# tdlf_01_04_2020_TOUCH.net
KiCad netlist of a schematic drawn in EAGLE
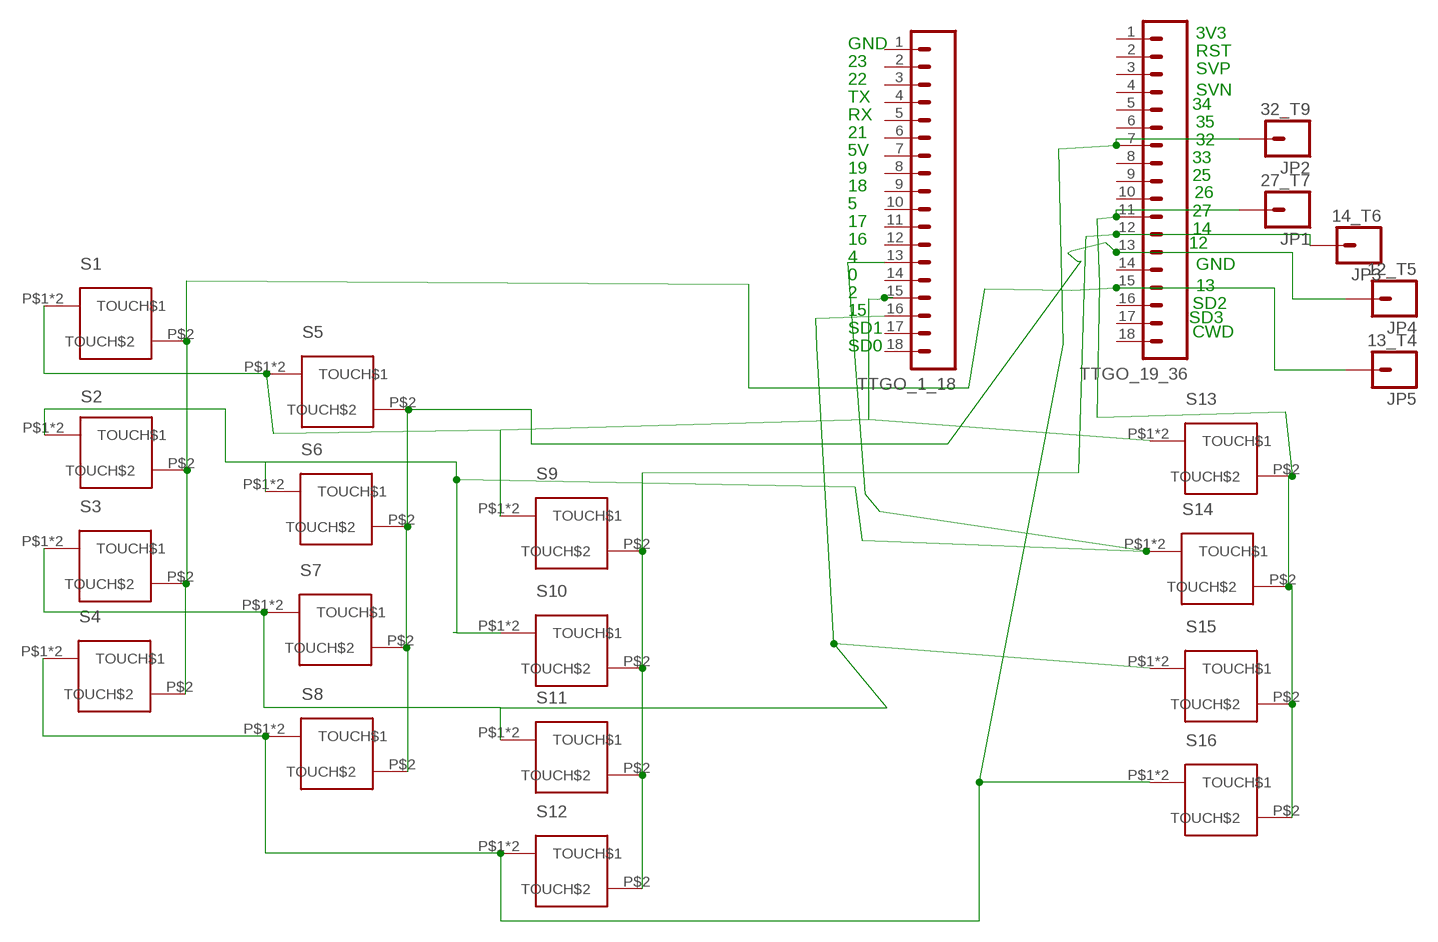
[diagram p0: schematic, sheet 1]

(export (version "E")
  (design (tool "Eeschema 10.0.6"))
  (components
    (comp (ref "JP1")
      (value "27_T7")
      (footprint "eagle-import:PAD-1.5X4.5")
      (libsource (lib "eagle-import") (part "M01SMD-4.5X1.5"))
    )
    (comp (ref "JP2")
      (value "32_T9")
      (footprint "eagle-import:PAD-1.5X4.5")
      (libsource (lib "eagle-import") (part "M01SMD-4.5X1.5"))
    )
    (comp (ref "JP3")
      (value "14_T6")
      (footprint "eagle-import:PAD-1.5X4.5")
      (libsource (lib "eagle-import") (part "M01SMD-4.5X1.5"))
    )
    (comp (ref "JP4")
      (value "12_T5")
      (footprint "eagle-import:PAD-1.5X4.5")
      (libsource (lib "eagle-import") (part "M01SMD-4.5X1.5"))
    )
    (comp (ref "JP5")
      (value "13_T4")
      (footprint "eagle-import:PAD-1.5X4.5")
      (libsource (lib "eagle-import") (part "M01SMD-4.5X1.5"))
    )
    (comp (ref "S1")
      (value "DUALCAPACITIVEBUTTON")
      (footprint "eagle-import:R1206")
      (libsource (lib "eagle-import") (part "DUALCAPACITIVEBUTTON"))
    )
    (comp (ref "S2")
      (value "DUALCAPACITIVEBUTTON")
      (footprint "eagle-import:R1206")
      (libsource (lib "eagle-import") (part "DUALCAPACITIVEBUTTON"))
    )
    (comp (ref "S3")
      (value "DUALCAPACITIVEBUTTON")
      (footprint "eagle-import:R1206")
      (libsource (lib "eagle-import") (part "DUALCAPACITIVEBUTTON"))
    )
    (comp (ref "S4")
      (value "DUALCAPACITIVEBUTTON")
      (footprint "eagle-import:R1206")
      (libsource (lib "eagle-import") (part "DUALCAPACITIVEBUTTON"))
    )
    (comp (ref "S5")
      (value "DUALCAPACITIVEBUTTON")
      (footprint "eagle-import:R1206")
      (libsource (lib "eagle-import") (part "DUALCAPACITIVEBUTTON"))
    )
    (comp (ref "S6")
      (value "DUALCAPACITIVEBUTTON")
      (footprint "eagle-import:R1206")
      (libsource (lib "eagle-import") (part "DUALCAPACITIVEBUTTON"))
    )
    (comp (ref "S7")
      (value "DUALCAPACITIVEBUTTON")
      (footprint "eagle-import:R1206")
      (libsource (lib "eagle-import") (part "DUALCAPACITIVEBUTTON"))
    )
    (comp (ref "S8")
      (value "DUALCAPACITIVEBUTTON")
      (footprint "eagle-import:R1206")
      (libsource (lib "eagle-import") (part "DUALCAPACITIVEBUTTON"))
    )
    (comp (ref "S9")
      (value "DUALCAPACITIVEBUTTON")
      (footprint "eagle-import:R1206")
      (libsource (lib "eagle-import") (part "DUALCAPACITIVEBUTTON"))
    )
    (comp (ref "S10")
      (value "DUALCAPACITIVEBUTTON")
      (footprint "eagle-import:R1206")
      (libsource (lib "eagle-import") (part "DUALCAPACITIVEBUTTON"))
    )
    (comp (ref "S11")
      (value "DUALCAPACITIVEBUTTON")
      (footprint "eagle-import:R1206")
      (libsource (lib "eagle-import") (part "DUALCAPACITIVEBUTTON"))
    )
    (comp (ref "S12")
      (value "DUALCAPACITIVEBUTTON")
      (footprint "eagle-import:R1206")
      (libsource (lib "eagle-import") (part "DUALCAPACITIVEBUTTON"))
    )
    (comp (ref "S13")
      (value "DUALCAPACITIVEBUTTON")
      (footprint "eagle-import:R1206")
      (libsource (lib "eagle-import") (part "DUALCAPACITIVEBUTTON"))
    )
    (comp (ref "S14")
      (value "DUALCAPACITIVEBUTTON")
      (footprint "eagle-import:R1206")
      (libsource (lib "eagle-import") (part "DUALCAPACITIVEBUTTON"))
    )
    (comp (ref "S15")
      (value "DUALCAPACITIVEBUTTON")
      (footprint "eagle-import:R1206")
      (libsource (lib "eagle-import") (part "DUALCAPACITIVEBUTTON"))
    )
    (comp (ref "S16")
      (value "DUALCAPACITIVEBUTTON")
      (footprint "eagle-import:R1206")
      (libsource (lib "eagle-import") (part "DUALCAPACITIVEBUTTON"))
    )
    (comp (ref "TTGO_1_18")
      (value "M18_")
      (footprint "eagle-import:1X18")
      (libsource (lib "eagle-import") (part "M18_"))
    )
    (comp (ref "TTGO_19_36")
      (value "M18_")
      (footprint "eagle-import:1X18")
      (libsource (lib "eagle-import") (part "M18_"))
    )
  )
  (nets
    (net (code "1") (name "Net-(JP1-1)") (class "Default")
      (node (ref "JP1") (pin "P$1") (pinfunction "1_P$1") (pintype "passive"))
      (node (ref "S13") (pin "P$2") (pinfunction "TOUCH$2_P$2") (pintype "bidirectional"))
      (node (ref "S14") (pin "P$2") (pinfunction "TOUCH$2_P$2") (pintype "bidirectional"))
      (node (ref "S15") (pin "P$2") (pinfunction "TOUCH$2_P$2") (pintype "bidirectional"))
      (node (ref "S16") (pin "P$2") (pinfunction "TOUCH$2_P$2") (pintype "bidirectional"))
      (node (ref "TTGO_19_36") (pin "11") (pinfunction "11_11") (pintype "passive"))
    )
    (net (code "2") (name "Net-(JP2-1)") (class "Default")
      (node (ref "JP2") (pin "P$1") (pinfunction "1_P$1") (pintype "passive"))
      (node (ref "S12") (pin "P$1") (pinfunction "TOUCH$1_P$1") (pintype "bidirectional"))
      (node (ref "S12") (pin "P$5") (pinfunction "TOUCH$1_P$5") (pintype "bidirectional"))
      (node (ref "S16") (pin "P$1") (pinfunction "TOUCH$1_P$1") (pintype "bidirectional"))
      (node (ref "S16") (pin "P$5") (pinfunction "TOUCH$1_P$5") (pintype "bidirectional"))
      (node (ref "S4") (pin "P$1") (pinfunction "TOUCH$1_P$1") (pintype "bidirectional"))
      (node (ref "S4") (pin "P$5") (pinfunction "TOUCH$1_P$5") (pintype "bidirectional"))
      (node (ref "S8") (pin "P$1") (pinfunction "TOUCH$1_P$1") (pintype "bidirectional"))
      (node (ref "S8") (pin "P$5") (pinfunction "TOUCH$1_P$5") (pintype "bidirectional"))
      (node (ref "TTGO_19_36") (pin "7") (pinfunction "7_7") (pintype "passive"))
    )
    (net (code "3") (name "Net-(JP3-1)") (class "Default")
      (node (ref "JP3") (pin "P$1") (pinfunction "1_P$1") (pintype "passive"))
      (node (ref "S10") (pin "P$2") (pinfunction "TOUCH$2_P$2") (pintype "bidirectional"))
      (node (ref "S11") (pin "P$2") (pinfunction "TOUCH$2_P$2") (pintype "bidirectional"))
      (node (ref "S12") (pin "P$2") (pinfunction "TOUCH$2_P$2") (pintype "bidirectional"))
      (node (ref "S9") (pin "P$2") (pinfunction "TOUCH$2_P$2") (pintype "bidirectional"))
      (node (ref "TTGO_19_36") (pin "12") (pinfunction "12_12") (pintype "passive"))
    )
    (net (code "4") (name "Net-(JP4-1)") (class "Default")
      (node (ref "JP4") (pin "P$1") (pinfunction "1_P$1") (pintype "passive"))
      (node (ref "S5") (pin "P$2") (pinfunction "TOUCH$2_P$2") (pintype "bidirectional"))
      (node (ref "S6") (pin "P$2") (pinfunction "TOUCH$2_P$2") (pintype "bidirectional"))
      (node (ref "S7") (pin "P$2") (pinfunction "TOUCH$2_P$2") (pintype "bidirectional"))
      (node (ref "S8") (pin "P$2") (pinfunction "TOUCH$2_P$2") (pintype "bidirectional"))
      (node (ref "TTGO_19_36") (pin "13") (pinfunction "13_13") (pintype "passive"))
    )
    (net (code "5") (name "Net-(JP5-1)") (class "Default")
      (node (ref "JP5") (pin "P$1") (pinfunction "1_P$1") (pintype "passive"))
      (node (ref "S1") (pin "P$2") (pinfunction "TOUCH$2_P$2") (pintype "bidirectional"))
      (node (ref "S2") (pin "P$2") (pinfunction "TOUCH$2_P$2") (pintype "bidirectional"))
      (node (ref "S3") (pin "P$2") (pinfunction "TOUCH$2_P$2") (pintype "bidirectional"))
      (node (ref "S4") (pin "P$2") (pinfunction "TOUCH$2_P$2") (pintype "bidirectional"))
      (node (ref "TTGO_19_36") (pin "15") (pinfunction "15_15") (pintype "passive"))
    )
    (net (code "6") (name "Net-(S1-TOUCH$1-PadP$1)") (class "Default")
      (node (ref "S1") (pin "P$1") (pinfunction "TOUCH$1_P$1") (pintype "bidirectional"))
      (node (ref "S1") (pin "P$5") (pinfunction "TOUCH$1_P$5") (pintype "bidirectional"))
      (node (ref "S13") (pin "P$1") (pinfunction "TOUCH$1_P$1") (pintype "bidirectional"))
      (node (ref "S13") (pin "P$5") (pinfunction "TOUCH$1_P$5") (pintype "bidirectional"))
      (node (ref "S5") (pin "P$1") (pinfunction "TOUCH$1_P$1") (pintype "bidirectional"))
      (node (ref "S5") (pin "P$5") (pinfunction "TOUCH$1_P$5") (pintype "bidirectional"))
      (node (ref "S9") (pin "P$1") (pinfunction "TOUCH$1_P$1") (pintype "bidirectional"))
      (node (ref "S9") (pin "P$5") (pinfunction "TOUCH$1_P$5") (pintype "bidirectional"))
      (node (ref "TTGO_1_18") (pin "15") (pinfunction "15_15") (pintype "passive"))
    )
    (net (code "7") (name "Net-(S10-TOUCH$1-PadP$1)") (class "Default")
      (node (ref "S10") (pin "P$1") (pinfunction "TOUCH$1_P$1") (pintype "bidirectional"))
      (node (ref "S10") (pin "P$5") (pinfunction "TOUCH$1_P$5") (pintype "bidirectional"))
      (node (ref "S14") (pin "P$1") (pinfunction "TOUCH$1_P$1") (pintype "bidirectional"))
      (node (ref "S14") (pin "P$5") (pinfunction "TOUCH$1_P$5") (pintype "bidirectional"))
      (node (ref "S2") (pin "P$1") (pinfunction "TOUCH$1_P$1") (pintype "bidirectional"))
      (node (ref "S2") (pin "P$5") (pinfunction "TOUCH$1_P$5") (pintype "bidirectional"))
      (node (ref "S6") (pin "P$1") (pinfunction "TOUCH$1_P$1") (pintype "bidirectional"))
      (node (ref "S6") (pin "P$5") (pinfunction "TOUCH$1_P$5") (pintype "bidirectional"))
      (node (ref "TTGO_1_18") (pin "13") (pinfunction "13_13") (pintype "passive"))
    )
    (net (code "8") (name "Net-(S11-TOUCH$1-PadP$1)") (class "Default")
      (node (ref "S11") (pin "P$1") (pinfunction "TOUCH$1_P$1") (pintype "bidirectional"))
      (node (ref "S11") (pin "P$5") (pinfunction "TOUCH$1_P$5") (pintype "bidirectional"))
      (node (ref "S15") (pin "P$1") (pinfunction "TOUCH$1_P$1") (pintype "bidirectional"))
      (node (ref "S15") (pin "P$5") (pinfunction "TOUCH$1_P$5") (pintype "bidirectional"))
      (node (ref "S3") (pin "P$1") (pinfunction "TOUCH$1_P$1") (pintype "bidirectional"))
      (node (ref "S3") (pin "P$5") (pinfunction "TOUCH$1_P$5") (pintype "bidirectional"))
      (node (ref "S7") (pin "P$1") (pinfunction "TOUCH$1_P$1") (pintype "bidirectional"))
      (node (ref "S7") (pin "P$5") (pinfunction "TOUCH$1_P$5") (pintype "bidirectional"))
      (node (ref "TTGO_1_18") (pin "16") (pinfunction "16_16") (pintype "passive"))
    )
    (net (code "9") (name "unconnected-(TTGO_1_18-Pad1)") (class "Default")
      (node (ref "TTGO_1_18") (pin "1") (pinfunction "1_1") (pintype "passive"))
    )
    (net (code "10") (name "unconnected-(TTGO_1_18-Pad2)") (class "Default")
      (node (ref "TTGO_1_18") (pin "2") (pinfunction "2_2") (pintype "passive"))
    )
    (net (code "11") (name "unconnected-(TTGO_1_18-Pad3)") (class "Default")
      (node (ref "TTGO_1_18") (pin "3") (pinfunction "3_3") (pintype "passive"))
    )
    (net (code "12") (name "unconnected-(TTGO_1_18-Pad4)") (class "Default")
      (node (ref "TTGO_1_18") (pin "4") (pinfunction "4_4") (pintype "passive"))
    )
    (net (code "13") (name "unconnected-(TTGO_1_18-Pad5)") (class "Default")
      (node (ref "TTGO_1_18") (pin "5") (pinfunction "5_5") (pintype "passive"))
    )
    (net (code "14") (name "unconnected-(TTGO_1_18-Pad6)") (class "Default")
      (node (ref "TTGO_1_18") (pin "6") (pinfunction "6_6") (pintype "passive"))
    )
    (net (code "15") (name "unconnected-(TTGO_1_18-Pad7)") (class "Default")
      (node (ref "TTGO_1_18") (pin "7") (pinfunction "7_7") (pintype "passive"))
    )
    (net (code "16") (name "unconnected-(TTGO_1_18-Pad8)") (class "Default")
      (node (ref "TTGO_1_18") (pin "8") (pinfunction "8_8") (pintype "passive"))
    )
    (net (code "17") (name "unconnected-(TTGO_1_18-Pad9)") (class "Default")
      (node (ref "TTGO_1_18") (pin "9") (pinfunction "9_9") (pintype "passive"))
    )
    (net (code "18") (name "unconnected-(TTGO_1_18-Pad10)") (class "Default")
      (node (ref "TTGO_1_18") (pin "10") (pinfunction "10_10") (pintype "passive"))
    )
    (net (code "19") (name "unconnected-(TTGO_1_18-Pad11)") (class "Default")
      (node (ref "TTGO_1_18") (pin "11") (pinfunction "11_11") (pintype "passive"))
    )
    (net (code "20") (name "unconnected-(TTGO_1_18-Pad12)") (class "Default")
      (node (ref "TTGO_1_18") (pin "12") (pinfunction "12_12") (pintype "passive"))
    )
    (net (code "21") (name "unconnected-(TTGO_1_18-Pad14)") (class "Default")
      (node (ref "TTGO_1_18") (pin "14") (pinfunction "14_14") (pintype "passive"))
    )
    (net (code "22") (name "unconnected-(TTGO_1_18-Pad17)") (class "Default")
      (node (ref "TTGO_1_18") (pin "17") (pinfunction "17_17") (pintype "passive"))
    )
    (net (code "23") (name "unconnected-(TTGO_1_18-Pad18)") (class "Default")
      (node (ref "TTGO_1_18") (pin "18") (pinfunction "18_18") (pintype "passive"))
    )
    (net (code "24") (name "unconnected-(TTGO_19_36-Pad1)") (class "Default")
      (node (ref "TTGO_19_36") (pin "1") (pinfunction "1_1") (pintype "passive"))
    )
    (net (code "25") (name "unconnected-(TTGO_19_36-Pad2)") (class "Default")
      (node (ref "TTGO_19_36") (pin "2") (pinfunction "2_2") (pintype "passive"))
    )
    (net (code "26") (name "unconnected-(TTGO_19_36-Pad3)") (class "Default")
      (node (ref "TTGO_19_36") (pin "3") (pinfunction "3_3") (pintype "passive"))
    )
    (net (code "27") (name "unconnected-(TTGO_19_36-Pad4)") (class "Default")
      (node (ref "TTGO_19_36") (pin "4") (pinfunction "4_4") (pintype "passive"))
    )
    (net (code "28") (name "unconnected-(TTGO_19_36-Pad5)") (class "Default")
      (node (ref "TTGO_19_36") (pin "5") (pinfunction "5_5") (pintype "passive"))
    )
    (net (code "29") (name "unconnected-(TTGO_19_36-Pad6)") (class "Default")
      (node (ref "TTGO_19_36") (pin "6") (pinfunction "6_6") (pintype "passive"))
    )
    (net (code "30") (name "unconnected-(TTGO_19_36-Pad8)") (class "Default")
      (node (ref "TTGO_19_36") (pin "8") (pinfunction "8_8") (pintype "passive"))
    )
    (net (code "31") (name "unconnected-(TTGO_19_36-Pad9)") (class "Default")
      (node (ref "TTGO_19_36") (pin "9") (pinfunction "9_9") (pintype "passive"))
    )
    (net (code "32") (name "unconnected-(TTGO_19_36-Pad10)") (class "Default")
      (node (ref "TTGO_19_36") (pin "10") (pinfunction "10_10") (pintype "passive"))
    )
    (net (code "33") (name "unconnected-(TTGO_19_36-Pad14)") (class "Default")
      (node (ref "TTGO_19_36") (pin "14") (pinfunction "14_14") (pintype "passive"))
    )
    (net (code "34") (name "unconnected-(TTGO_19_36-Pad16)") (class "Default")
      (node (ref "TTGO_19_36") (pin "16") (pinfunction "16_16") (pintype "passive"))
    )
    (net (code "35") (name "unconnected-(TTGO_19_36-Pad17)") (class "Default")
      (node (ref "TTGO_19_36") (pin "17") (pinfunction "17_17") (pintype "passive"))
    )
    (net (code "36") (name "unconnected-(TTGO_19_36-Pad18)") (class "Default")
      (node (ref "TTGO_19_36") (pin "18") (pinfunction "18_18") (pintype "passive"))
    )
  )
)
